# SSR_3_3V.net
KiCad netlist of a schematic drawn in EAGLE
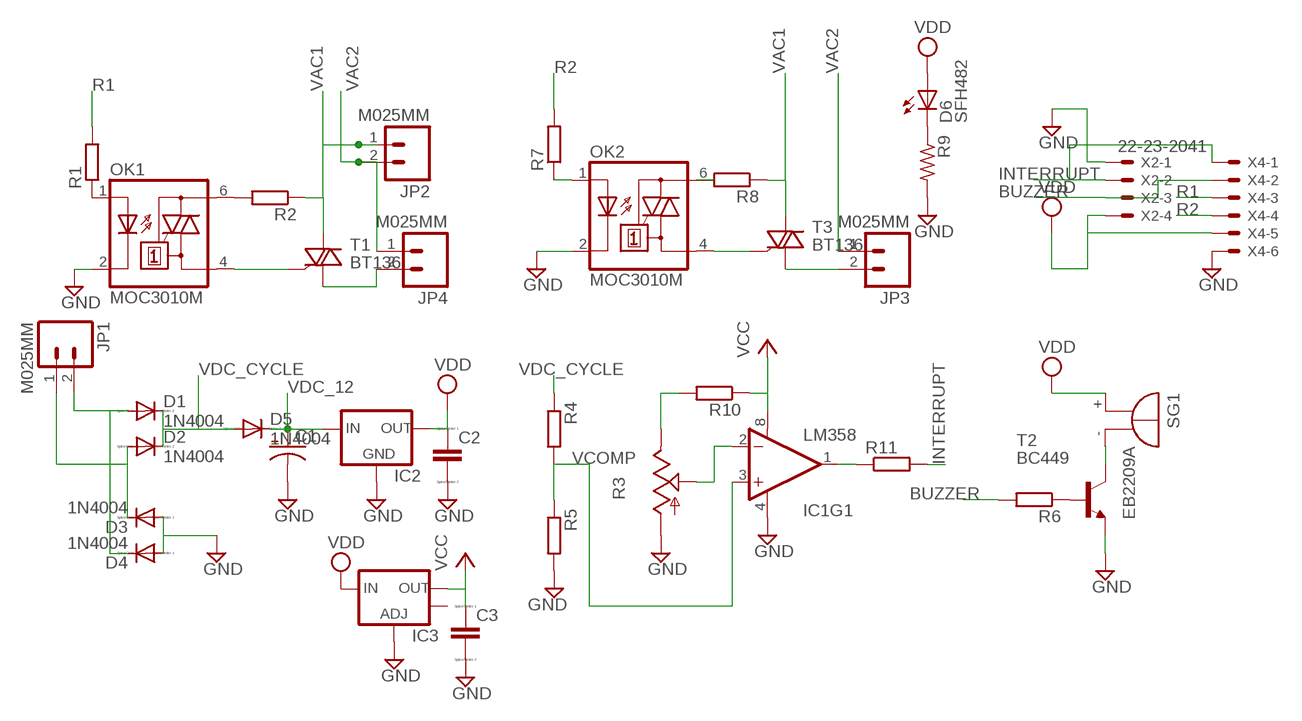
[diagram p0: schematic, sheet 1]

(export (version "E")
  (design (tool "Eeschema 10.0.6"))
  (components
    (comp (ref "C1")
      (value "CPOL-USE3.5-10")
      (footprint "eagle-import:E3,5-10")
      (libsource (lib "eagle-import") (part "CPOL-USE3.5-10"))
    )
    (comp (ref "C2")
      (value "CC1206")
      (footprint "eagle-import:C1206")
      (libsource (lib "eagle-import") (part "CC1206"))
    )
    (comp (ref "C3")
      (value "CC1206")
      (footprint "eagle-import:C1206")
      (libsource (lib "eagle-import") (part "CC1206"))
    )
    (comp (ref "D1")
      (value "1N4004")
      (footprint "eagle-import:DO41-10")
      (libsource (lib "eagle-import") (part "1N4004"))
    )
    (comp (ref "D2")
      (value "1N4004")
      (footprint "eagle-import:DO41-10")
      (libsource (lib "eagle-import") (part "1N4004"))
    )
    (comp (ref "D3")
      (value "1N4004")
      (footprint "eagle-import:DO41-10")
      (libsource (lib "eagle-import") (part "1N4004"))
    )
    (comp (ref "D4")
      (value "1N4004")
      (footprint "eagle-import:DO41-10")
      (libsource (lib "eagle-import") (part "1N4004"))
    )
    (comp (ref "D5")
      (value "1N4004")
      (footprint "eagle-import:DO41-10")
      (libsource (lib "eagle-import") (part "1N4004"))
    )
    (comp (ref "D6")
      (value "SFH482")
      (footprint "eagle-import:SFH482")
      (libsource (lib "eagle-import") (part "SFH482"))
    )
    (comp (ref "IC1")
      (value "LM358")
      (footprint "eagle-import:DIP08")
      (libsource (lib "eagle-import") (part "LM358"))
    )
    (comp (ref "IC2")
      (value "V_REG_78XX-TO-220")
      (footprint "eagle-import:TO-220-ALT")
      (libsource (lib "eagle-import") (part "V_REG_78XX-TO-220"))
    )
    (comp (ref "IC3")
      (value "V_REG_LM1117SOT223")
      (footprint "eagle-import:SOT223")
      (libsource (lib "eagle-import") (part "V_REG_LM1117SOT223"))
    )
    (comp (ref "JP1")
      (value "M025MM")
      (footprint "eagle-import:SCREWTERMINAL-5MM-2")
      (libsource (lib "eagle-import") (part "M025MM"))
    )
    (comp (ref "JP2")
      (value "M025MM")
      (footprint "eagle-import:SCREWTERMINAL-5MM-2")
      (libsource (lib "eagle-import") (part "M025MM"))
    )
    (comp (ref "JP3")
      (value "M025MM")
      (footprint "eagle-import:SCREWTERMINAL-5MM-2")
      (libsource (lib "eagle-import") (part "M025MM"))
    )
    (comp (ref "JP4")
      (value "M025MM")
      (footprint "eagle-import:SCREWTERMINAL-5MM-2")
      (libsource (lib "eagle-import") (part "M025MM"))
    )
    (comp (ref "OK1")
      (value "MOC3010M")
      (footprint "eagle-import:DIL06")
      (fields (field (name "MF") "FAIRCHILD SEMICONDUCTOR") (field (name "MPN") "MOC3010-M"))
      (libsource (lib "eagle-import") (part "MOC30M10"))
    )
    (comp (ref "OK2")
      (value "MOC3010M")
      (footprint "eagle-import:DIL06")
      (fields (field (name "MF") "FAIRCHILD SEMICONDUCTOR") (field (name "MPN") "MOC3010-M"))
      (libsource (lib "eagle-import") (part "MOC30M10"))
    )
    (comp (ref "R1")
      (value "R-EU_0204/7")
      (footprint "eagle-import:0204_7")
      (libsource (lib "eagle-import") (part "R-EU_0204/7"))
    )
    (comp (ref "R2")
      (value "R-EU_0204/7")
      (footprint "eagle-import:0204_7")
      (libsource (lib "eagle-import") (part "R-EU_0204/7"))
    )
    (comp (ref "R3")
      (value "TRIM_US-CA9V")
      (footprint "eagle-import:CA9V")
      (libsource (lib "eagle-import") (part "TRIM_US-CA9V"))
    )
    (comp (ref "R4")
      (value "R-EU_0207/12")
      (footprint "eagle-import:0207_12")
      (libsource (lib "eagle-import") (part "R-EU_0207/12"))
    )
    (comp (ref "R5")
      (value "R-EU_0204/7")
      (footprint "eagle-import:0204_7")
      (libsource (lib "eagle-import") (part "R-EU_0204/7"))
    )
    (comp (ref "R6")
      (value "R-EU_0204/7")
      (footprint "eagle-import:0204_7")
      (libsource (lib "eagle-import") (part "R-EU_0204/7"))
    )
    (comp (ref "R7")
      (value "R-EU_0204/7")
      (footprint "eagle-import:0204_7")
      (libsource (lib "eagle-import") (part "R-EU_0204/7"))
    )
    (comp (ref "R8")
      (value "R-EU_0204/7")
      (footprint "eagle-import:0204_7")
      (libsource (lib "eagle-import") (part "R-EU_0204/7"))
    )
    (comp (ref "R9")
      (value "R-US_0207/10")
      (footprint "eagle-import:0207_10")
      (libsource (lib "eagle-import") (part "R-US_0207/10"))
    )
    (comp (ref "R10")
      (value "R-EU_0204/7")
      (footprint "eagle-import:0204_7")
      (libsource (lib "eagle-import") (part "R-EU_0204/7"))
    )
    (comp (ref "R11")
      (value "R-EU_0207/12")
      (footprint "eagle-import:0207_12")
      (libsource (lib "eagle-import") (part "R-EU_0207/12"))
    )
    (comp (ref "SG1")
      (value "EB2209A")
      (footprint "eagle-import:EB2209A")
      (libsource (lib "eagle-import") (part "EB2209A"))
    )
    (comp (ref "T1")
      (value "BT136")
      (footprint "eagle-import:TO220AB")
      (libsource (lib "eagle-import") (part "BT136"))
    )
    (comp (ref "T2")
      (value "BC449")
      (footprint "eagle-import:TO92-EBC")
      (libsource (lib "eagle-import") (part "BC449"))
    )
    (comp (ref "T3")
      (value "BT136")
      (footprint "eagle-import:TO220AB")
      (libsource (lib "eagle-import") (part "BT136"))
    )
    (comp (ref "X2")
      (value "22-23-2041")
      (footprint "eagle-import:22-23-2041")
      (fields (field (name "MF") "MOLEX"))
      (libsource (lib "eagle-import") (part "22-23-2041"))
    )
    (comp (ref "X4")
      (value "22-23-2061")
      (footprint "eagle-import:22-23-2061")
      (fields (field (name "MF") "MOLEX"))
      (libsource (lib "eagle-import") (part "22-23-2061"))
    )
  )
  (nets
    (net (code "1") (name "/BUZZER") (class "Default")
      (node (ref "R6") (pin "2") (pinfunction "2_2") (pintype "passive"))
      (node (ref "X2") (pin "3") (pinfunction "S_3") (pintype "passive"))
      (node (ref "X4") (pin "2") (pinfunction "S_2") (pintype "passive"))
    )
    (net (code "2") (name "/INTERRUPT") (class "Default")
      (node (ref "R11") (pin "2") (pinfunction "2_2") (pintype "passive"))
      (node (ref "X2") (pin "2") (pinfunction "S_2") (pintype "passive"))
      (node (ref "X4") (pin "1") (pinfunction "S_1") (pintype "passive"))
    )
    (net (code "3") (name "/R1") (class "Default")
      (node (ref "R1") (pin "2") (pinfunction "2_2") (pintype "passive"))
      (node (ref "X4") (pin "3") (pinfunction "S_3") (pintype "passive"))
    )
    (net (code "4") (name "/R2") (class "Default")
      (node (ref "R7") (pin "2") (pinfunction "2_2") (pintype "passive"))
      (node (ref "X4") (pin "4") (pinfunction "S_4") (pintype "passive"))
    )
    (net (code "5") (name "/VAC1") (class "Default")
      (node (ref "JP2") (pin "1") (pinfunction "1_1") (pintype "passive"))
      (node (ref "R2") (pin "1") (pinfunction "1_1") (pintype "passive"))
      (node (ref "R8") (pin "1") (pinfunction "1_1") (pintype "passive"))
      (node (ref "T1") (pin "2") (pinfunction "A2_2") (pintype "passive"))
      (node (ref "T3") (pin "2") (pinfunction "A2_2") (pintype "passive"))
    )
    (net (code "6") (name "/VAC2") (class "Default")
      (node (ref "JP2") (pin "2") (pinfunction "2_2") (pintype "passive"))
      (node (ref "JP3") (pin "1") (pinfunction "1_1") (pintype "passive"))
      (node (ref "JP4") (pin "1") (pinfunction "1_1") (pintype "passive"))
    )
    (net (code "7") (name "/VCOMP") (class "Default")
      (node (ref "IC1") (pin "3") (pinfunction "+IN_3") (pintype "input"))
      (node (ref "R4") (pin "2") (pinfunction "2_2") (pintype "passive"))
      (node (ref "R5") (pin "1") (pinfunction "1_1") (pintype "passive"))
    )
    (net (code "8") (name "/VDC_12") (class "Default")
      (node (ref "C1") (pin "+") (pinfunction "+_+") (pintype "passive"))
      (node (ref "D5") (pin "C") (pinfunction "C_C") (pintype "passive"))
      (node (ref "IC2") (pin "IN") (pinfunction "IN_IN") (pintype "input"))
    )
    (net (code "9") (name "/VDC_CYCLE") (class "Default")
      (node (ref "D1") (pin "C") (pinfunction "C_C") (pintype "passive"))
      (node (ref "D2") (pin "C") (pinfunction "C_C") (pintype "passive"))
      (node (ref "D5") (pin "A") (pinfunction "A_A") (pintype "passive"))
      (node (ref "R4") (pin "1") (pinfunction "1_1") (pintype "passive"))
    )
    (net (code "10") (name "GND") (class "Default")
      (node (ref "C1") (pin "-") (pinfunction "-_-") (pintype "passive"))
      (node (ref "C2") (pin "2") (pinfunction "2_2") (pintype "passive"))
      (node (ref "C3") (pin "2") (pinfunction "2_2") (pintype "passive"))
      (node (ref "D3") (pin "A") (pinfunction "A_A") (pintype "passive"))
      (node (ref "D4") (pin "A") (pinfunction "A_A") (pintype "passive"))
      (node (ref "IC1") (pin "4") (pinfunction "V-_4") (pintype "power_in"))
      (node (ref "IC2") (pin "GND") (pinfunction "GND_GND") (pintype "input"))
      (node (ref "IC3") (pin "1") (pinfunction "ADJ_1") (pintype "input"))
      (node (ref "OK1") (pin "2") (pinfunction "C_2") (pintype "passive"))
      (node (ref "OK2") (pin "2") (pinfunction "C_2") (pintype "passive"))
      (node (ref "R3") (pin "A") (pinfunction "A_A") (pintype "passive"))
      (node (ref "R5") (pin "2") (pinfunction "2_2") (pintype "passive"))
      (node (ref "R9") (pin "2") (pinfunction "2_2") (pintype "passive"))
      (node (ref "T2") (pin "E") (pinfunction "E_E") (pintype "passive"))
      (node (ref "X2") (pin "1") (pinfunction "S_1") (pintype "passive"))
      (node (ref "X4") (pin "6") (pinfunction "S_6") (pintype "passive"))
    )
    (net (code "11") (name "Net-(D1-PadA)") (class "Default")
      (node (ref "D1") (pin "A") (pinfunction "A_A") (pintype "passive"))
      (node (ref "D4") (pin "C") (pinfunction "C_C") (pintype "passive"))
      (node (ref "JP1") (pin "2") (pinfunction "2_2") (pintype "passive"))
    )
    (net (code "12") (name "Net-(D2-PadA)") (class "Default")
      (node (ref "D2") (pin "A") (pinfunction "A_A") (pintype "passive"))
      (node (ref "D3") (pin "C") (pinfunction "C_C") (pintype "passive"))
      (node (ref "JP1") (pin "1") (pinfunction "1_1") (pintype "passive"))
    )
    (net (code "13") (name "Net-(D6-C)") (class "Default")
      (node (ref "D6") (pin "K") (pinfunction "C_K") (pintype "passive"))
      (node (ref "R9") (pin "1") (pinfunction "1_1") (pintype "passive"))
    )
    (net (code "14") (name "Net-(IC1A--IN)") (class "Default")
      (node (ref "IC1") (pin "2") (pinfunction "-IN_2") (pintype "input"))
      (node (ref "R3") (pin "S") (pinfunction "S_S") (pintype "passive"))
    )
    (net (code "15") (name "Net-(IC1A-OUT)") (class "Default")
      (node (ref "IC1") (pin "1") (pinfunction "OUT_1") (pintype "output"))
      (node (ref "R11") (pin "1") (pinfunction "1_1") (pintype "passive"))
    )
    (net (code "16") (name "Net-(OK1-A)") (class "Default")
      (node (ref "OK1") (pin "1") (pinfunction "A_1") (pintype "passive"))
      (node (ref "R1") (pin "1") (pinfunction "1_1") (pintype "passive"))
    )
    (net (code "17") (name "Net-(OK1-A1)") (class "Default")
      (node (ref "OK1") (pin "4") (pinfunction "A1_4") (pintype "passive"))
      (node (ref "T1") (pin "3") (pinfunction "G_3") (pintype "passive"))
    )
    (net (code "18") (name "Net-(OK1-A2)") (class "Default")
      (node (ref "OK1") (pin "6") (pinfunction "A2_6") (pintype "passive"))
      (node (ref "R2") (pin "2") (pinfunction "2_2") (pintype "passive"))
    )
    (net (code "19") (name "Net-(OK2-A)") (class "Default")
      (node (ref "OK2") (pin "1") (pinfunction "A_1") (pintype "passive"))
      (node (ref "R7") (pin "1") (pinfunction "1_1") (pintype "passive"))
    )
    (net (code "20") (name "Net-(OK2-A1)") (class "Default")
      (node (ref "OK2") (pin "4") (pinfunction "A1_4") (pintype "passive"))
      (node (ref "T3") (pin "3") (pinfunction "G_3") (pintype "passive"))
    )
    (net (code "21") (name "Net-(OK2-A2)") (class "Default")
      (node (ref "OK2") (pin "6") (pinfunction "A2_6") (pintype "passive"))
      (node (ref "R8") (pin "2") (pinfunction "2_2") (pintype "passive"))
    )
    (net (code "22") (name "Net-(R6-Pad1)") (class "Default")
      (node (ref "R6") (pin "1") (pinfunction "1_1") (pintype "passive"))
      (node (ref "T2") (pin "B") (pinfunction "B_B") (pintype "passive"))
    )
    (net (code "23") (name "Net-(R10-Pad2)") (class "Default")
      (node (ref "R10") (pin "2") (pinfunction "2_2") (pintype "passive"))
      (node (ref "R3") (pin "E") (pinfunction "E_E") (pintype "passive"))
    )
    (net (code "24") (name "Net-(SG1-Pad-)") (class "Default")
      (node (ref "SG1") (pin "-") (pinfunction "-_-") (pintype "passive"))
      (node (ref "T2") (pin "C") (pinfunction "C_C") (pintype "passive"))
    )
    (net (code "25") (name "Net-(T1-A1)") (class "Default")
      (node (ref "JP4") (pin "2") (pinfunction "2_2") (pintype "passive"))
      (node (ref "T1") (pin "1") (pinfunction "A1_1") (pintype "passive"))
    )
    (net (code "26") (name "Net-(T3-A1)") (class "Default")
      (node (ref "JP3") (pin "2") (pinfunction "2_2") (pintype "passive"))
      (node (ref "T3") (pin "1") (pinfunction "A1_1") (pintype "passive"))
    )
    (net (code "27") (name "VCC") (class "Default")
      (node (ref "C3") (pin "1") (pinfunction "1_1") (pintype "passive"))
      (node (ref "IC1") (pin "8") (pinfunction "V+_8") (pintype "power_in"))
      (node (ref "IC3") (pin "2") (pinfunction "OUT_2") (pintype "output"))
      (node (ref "R10") (pin "1") (pinfunction "1_1") (pintype "passive"))
    )
    (net (code "28") (name "VDD") (class "Default")
      (node (ref "C2") (pin "1") (pinfunction "1_1") (pintype "passive"))
      (node (ref "D6") (pin "A") (pinfunction "A_A") (pintype "passive"))
      (node (ref "IC2") (pin "OUT") (pinfunction "OUT_OUT") (pintype "output"))
      (node (ref "IC3") (pin "3") (pinfunction "IN_3") (pintype "input"))
      (node (ref "SG1") (pin "+") (pinfunction "+_+") (pintype "passive"))
      (node (ref "X2") (pin "4") (pinfunction "S_4") (pintype "passive"))
      (node (ref "X4") (pin "5") (pinfunction "S_5") (pintype "passive"))
    )
    (net (code "29") (name "unconnected-(IC3-OUT-Pad4)") (class "Default")
      (node (ref "IC3") (pin "4") (pinfunction "OUT_4") (pintype "output"))
    )
  )
)
